# do.net
KiCad netlist of a schematic drawn in Altium Designer
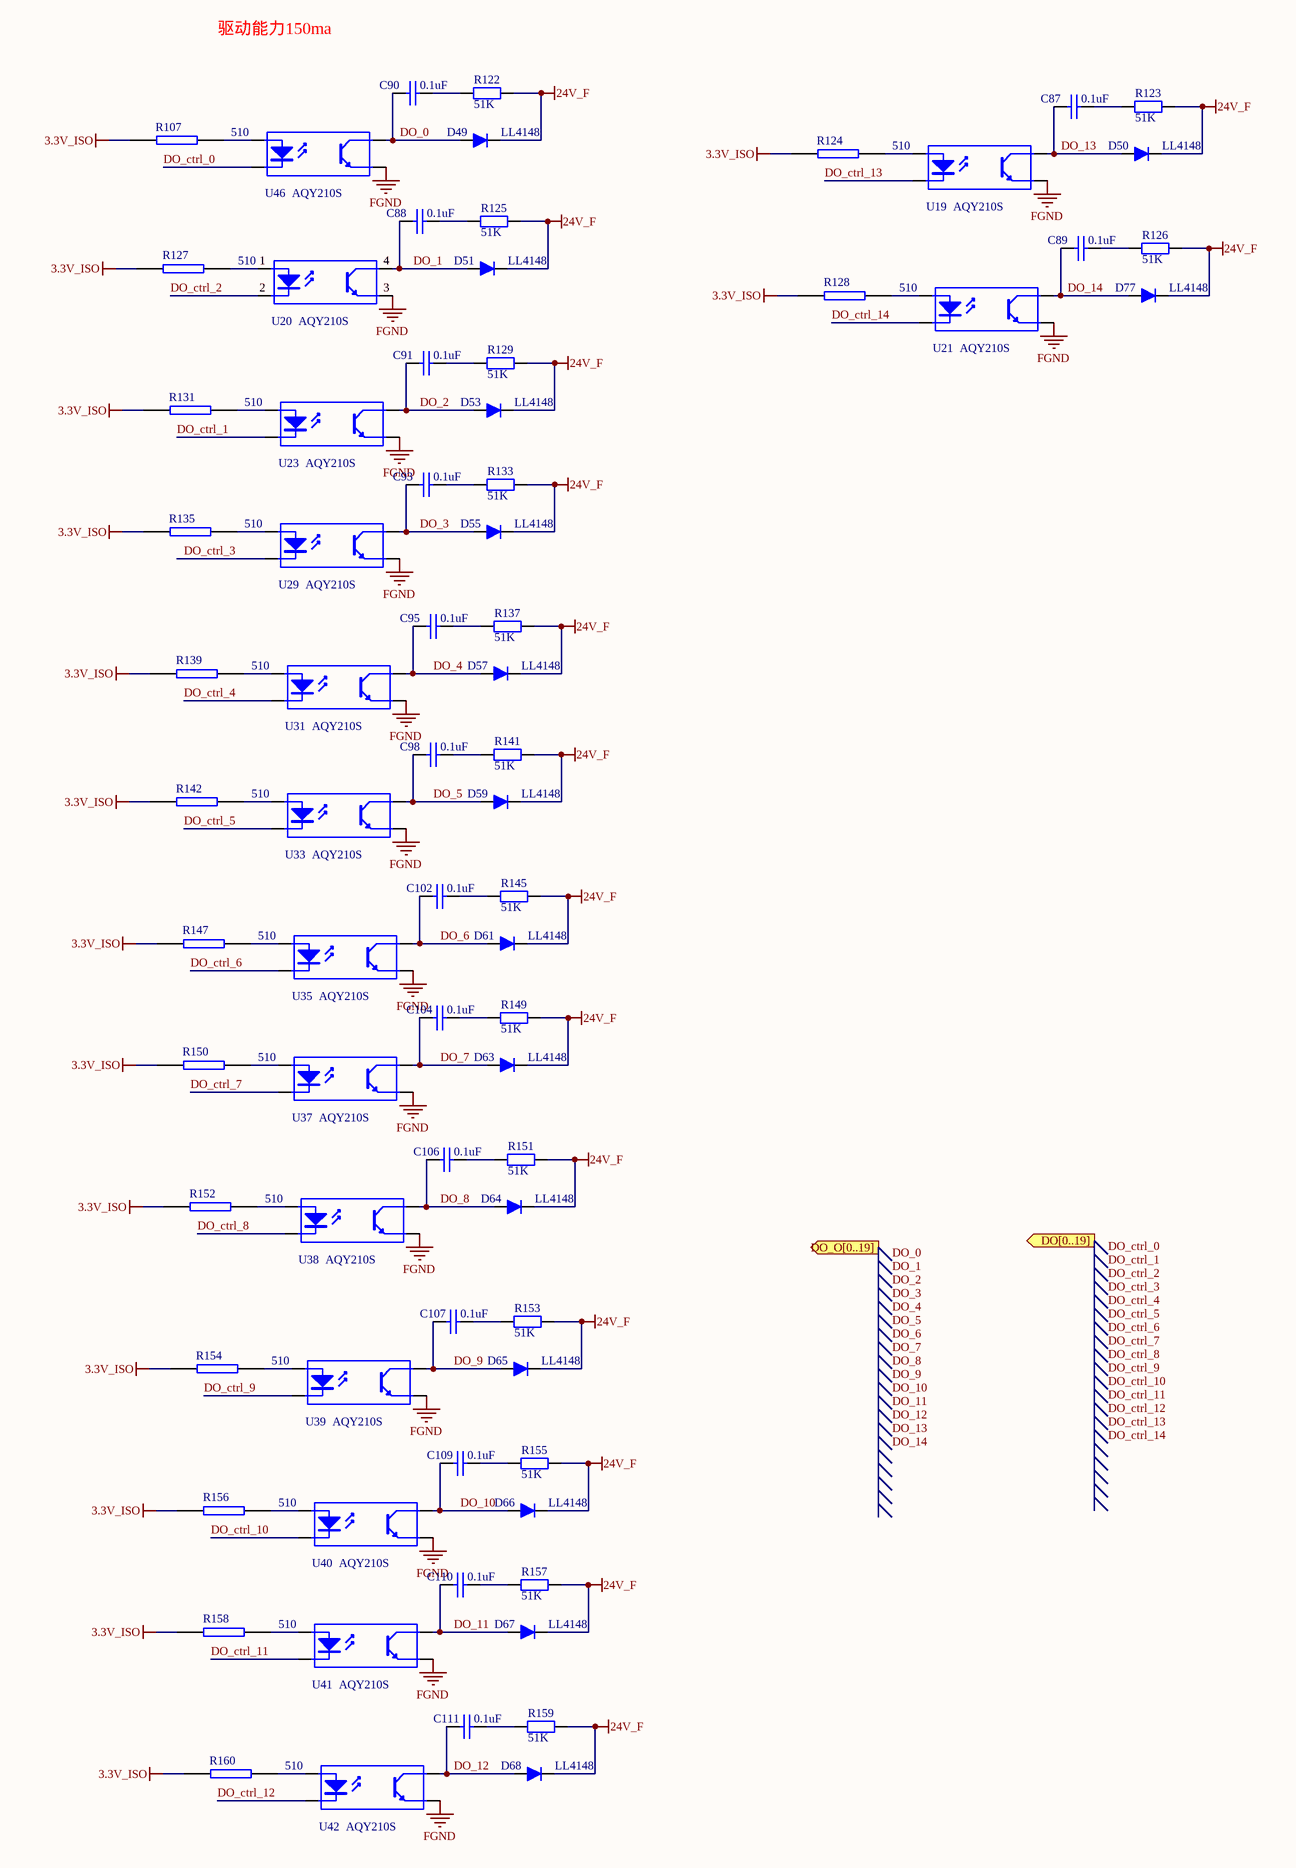
[diagram p0: do.SchDoc]

(export (version "E")
  (design (tool "Eeschema 10.0.6"))
  (components
    (comp (ref "C87")
      (value "0.1uF")
      (footprint "0603C")
      (description "Capacitor")
      (libsource (lib "*") (part "CAP"))
    )
    (comp (ref "C88")
      (value "0.1uF")
      (footprint "0603C")
      (description "Capacitor")
      (libsource (lib "*") (part "CAP"))
    )
    (comp (ref "C89")
      (value "0.1uF")
      (footprint "0603C")
      (description "Capacitor")
      (libsource (lib "*") (part "CAP"))
    )
    (comp (ref "C90")
      (value "0.1uF")
      (footprint "0603C")
      (description "Capacitor")
      (libsource (lib "*") (part "CAP"))
    )
    (comp (ref "C91")
      (value "0.1uF")
      (footprint "0603C")
      (description "Capacitor")
      (libsource (lib "*") (part "CAP"))
    )
    (comp (ref "C93")
      (value "0.1uF")
      (footprint "0603C")
      (description "Capacitor")
      (libsource (lib "*") (part "CAP"))
    )
    (comp (ref "C95")
      (value "0.1uF")
      (footprint "0603C")
      (description "Capacitor")
      (libsource (lib "*") (part "CAP"))
    )
    (comp (ref "C98")
      (value "0.1uF")
      (footprint "0603C")
      (description "Capacitor")
      (libsource (lib "*") (part "CAP"))
    )
    (comp (ref "C102")
      (value "0.1uF")
      (footprint "0603C")
      (description "Capacitor")
      (libsource (lib "*") (part "CAP"))
    )
    (comp (ref "C104")
      (value "0.1uF")
      (footprint "0603C")
      (description "Capacitor")
      (libsource (lib "*") (part "CAP"))
    )
    (comp (ref "C106")
      (value "0.1uF")
      (footprint "0603C")
      (description "Capacitor")
      (libsource (lib "*") (part "CAP"))
    )
    (comp (ref "C107")
      (value "0.1uF")
      (footprint "0603C")
      (description "Capacitor")
      (libsource (lib "*") (part "CAP"))
    )
    (comp (ref "C109")
      (value "0.1uF")
      (footprint "0603C")
      (description "Capacitor")
      (libsource (lib "*") (part "CAP"))
    )
    (comp (ref "C110")
      (value "0.1uF")
      (footprint "0603C")
      (description "Capacitor")
      (libsource (lib "*") (part "CAP"))
    )
    (comp (ref "C111")
      (value "0.1uF")
      (footprint "0603C")
      (description "Capacitor")
      (libsource (lib "*") (part "CAP"))
    )
    (comp (ref "D49")
      (value "LL4148")
      (footprint "DO-213AB/LL34/MiniMELF")
      (description "VISHAY,LL4148,圆柱体MiniMELF100V/2A,ROHS")
      (libsource (lib "Device2018") (part "LL4148"))
    )
    (comp (ref "D50")
      (value "LL4148")
      (footprint "DO-213AB/LL34/MiniMELF")
      (description "VISHAY,LL4148,圆柱体MiniMELF100V/2A,ROHS")
      (libsource (lib "Device2018") (part "LL4148"))
    )
    (comp (ref "D51")
      (value "LL4148")
      (footprint "DO-213AB/LL34/MiniMELF")
      (description "VISHAY,LL4148,圆柱体MiniMELF100V/2A,ROHS")
      (libsource (lib "Device2018") (part "LL4148"))
    )
    (comp (ref "D53")
      (value "LL4148")
      (footprint "DO-213AB/LL34/MiniMELF")
      (description "VISHAY,LL4148,圆柱体MiniMELF100V/2A,ROHS")
      (libsource (lib "Device2018") (part "LL4148"))
    )
    (comp (ref "D55")
      (value "LL4148")
      (footprint "DO-213AB/LL34/MiniMELF")
      (description "VISHAY,LL4148,圆柱体MiniMELF100V/2A,ROHS")
      (libsource (lib "Device2018") (part "LL4148"))
    )
    (comp (ref "D57")
      (value "LL4148")
      (footprint "DO-213AB/LL34/MiniMELF")
      (description "VISHAY,LL4148,圆柱体MiniMELF100V/2A,ROHS")
      (libsource (lib "Device2018") (part "LL4148"))
    )
    (comp (ref "D59")
      (value "LL4148")
      (footprint "DO-213AB/LL34/MiniMELF")
      (description "VISHAY,LL4148,圆柱体MiniMELF100V/2A,ROHS")
      (libsource (lib "Device2018") (part "LL4148"))
    )
    (comp (ref "D61")
      (value "LL4148")
      (footprint "DO-213AB/LL34/MiniMELF")
      (description "VISHAY,LL4148,圆柱体MiniMELF100V/2A,ROHS")
      (libsource (lib "Device2018") (part "LL4148"))
    )
    (comp (ref "D63")
      (value "LL4148")
      (footprint "DO-213AB/LL34/MiniMELF")
      (description "VISHAY,LL4148,圆柱体MiniMELF100V/2A,ROHS")
      (libsource (lib "Device2018") (part "LL4148"))
    )
    (comp (ref "D64")
      (value "LL4148")
      (footprint "DO-213AB/LL34/MiniMELF")
      (description "VISHAY,LL4148,圆柱体MiniMELF100V/2A,ROHS")
      (libsource (lib "Device2018") (part "LL4148"))
    )
    (comp (ref "D65")
      (value "LL4148")
      (footprint "DO-213AB/LL34/MiniMELF")
      (description "VISHAY,LL4148,圆柱体MiniMELF100V/2A,ROHS")
      (libsource (lib "Device2018") (part "LL4148"))
    )
    (comp (ref "D66")
      (value "LL4148")
      (footprint "DO-213AB/LL34/MiniMELF")
      (description "VISHAY,LL4148,圆柱体MiniMELF100V/2A,ROHS")
      (libsource (lib "Device2018") (part "LL4148"))
    )
    (comp (ref "D67")
      (value "LL4148")
      (footprint "DO-213AB/LL34/MiniMELF")
      (description "VISHAY,LL4148,圆柱体MiniMELF100V/2A,ROHS")
      (libsource (lib "Device2018") (part "LL4148"))
    )
    (comp (ref "D68")
      (value "LL4148")
      (footprint "DO-213AB/LL34/MiniMELF")
      (description "VISHAY,LL4148,圆柱体MiniMELF100V/2A,ROHS")
      (libsource (lib "Device2018") (part "LL4148"))
    )
    (comp (ref "D77")
      (value "LL4148")
      (footprint "DO-213AB/LL34/MiniMELF")
      (description "VISHAY,LL4148,圆柱体MiniMELF100V/2A,ROHS")
      (libsource (lib "Device2018") (part "LL4148"))
    )
    (comp (ref "R107") (value "510") (footprint "0603R") (libsource (lib "*") (part "RES2")))
    (comp (ref "R122") (value "51K") (footprint "0603R") (libsource (lib "MQlibrary") (part "Res0805M")))
    (comp (ref "R123") (value "51K") (footprint "0603R") (libsource (lib "MQlibrary") (part "Res0805M")))
    (comp (ref "R124") (value "510") (footprint "0603R") (libsource (lib "*") (part "RES2")))
    (comp (ref "R125") (value "51K") (footprint "0603R") (libsource (lib "MQlibrary") (part "Res0805M")))
    (comp (ref "R126") (value "51K") (footprint "0603R") (libsource (lib "MQlibrary") (part "Res0805M")))
    (comp (ref "R127") (value "510") (footprint "0603R") (libsource (lib "*") (part "RES2")))
    (comp (ref "R128") (value "510") (footprint "0603R") (libsource (lib "*") (part "RES2")))
    (comp (ref "R129") (value "51K") (footprint "0603R") (libsource (lib "MQlibrary") (part "Res0805M")))
    (comp (ref "R131") (value "510") (footprint "0603R") (libsource (lib "*") (part "RES2")))
    (comp (ref "R133") (value "51K") (footprint "0603R") (libsource (lib "MQlibrary") (part "Res0805M")))
    (comp (ref "R135") (value "510") (footprint "0603R") (libsource (lib "*") (part "RES2")))
    (comp (ref "R137") (value "51K") (footprint "0603R") (libsource (lib "MQlibrary") (part "Res0805M")))
    (comp (ref "R139") (value "510") (footprint "0603R") (libsource (lib "*") (part "RES2")))
    (comp (ref "R141") (value "51K") (footprint "0603R") (libsource (lib "MQlibrary") (part "Res0805M")))
    (comp (ref "R142") (value "510") (footprint "0603R") (libsource (lib "*") (part "RES2")))
    (comp (ref "R145") (value "51K") (footprint "0603R") (libsource (lib "MQlibrary") (part "Res0805M")))
    (comp (ref "R147") (value "510") (footprint "0603R") (libsource (lib "*") (part "RES2")))
    (comp (ref "R149") (value "51K") (footprint "0603R") (libsource (lib "MQlibrary") (part "Res0805M")))
    (comp (ref "R150") (value "510") (footprint "0603R") (libsource (lib "*") (part "RES2")))
    (comp (ref "R151") (value "51K") (footprint "0603R") (libsource (lib "MQlibrary") (part "Res0805M")))
    (comp (ref "R152") (value "510") (footprint "0603R") (libsource (lib "*") (part "RES2")))
    (comp (ref "R153") (value "51K") (footprint "0603R") (libsource (lib "MQlibrary") (part "Res0805M")))
    (comp (ref "R154") (value "510") (footprint "0603R") (libsource (lib "*") (part "RES2")))
    (comp (ref "R155") (value "51K") (footprint "0603R") (libsource (lib "MQlibrary") (part "Res0805M")))
    (comp (ref "R156") (value "510") (footprint "0603R") (libsource (lib "*") (part "RES2")))
    (comp (ref "R157") (value "51K") (footprint "0603R") (libsource (lib "MQlibrary") (part "Res0805M")))
    (comp (ref "R158") (value "510") (footprint "0603R") (libsource (lib "*") (part "RES2")))
    (comp (ref "R159") (value "51K") (footprint "0603R") (libsource (lib "MQlibrary") (part "Res0805M")))
    (comp (ref "R160") (value "510") (footprint "0603R") (libsource (lib "*") (part "RES2")))
    (comp (ref "U19")
      (value "AQY210S")
      (footprint "sop4")
      (description "4-Pin Phototransistor Optocoupler")
      (fields (field (name "PUBLISHER") "Altium Limited"))
      (libsource (lib "Miscellaneous Devices") (part "Optoisolator1"))
    )
    (comp (ref "U20")
      (value "AQY210S")
      (footprint "sop4")
      (description "4-Pin Phototransistor Optocoupler")
      (fields (field (name "PUBLISHER") "Altium Limited"))
      (libsource (lib "") (part "Optoisolator1_1"))
    )
    (comp (ref "U21")
      (value "AQY210S")
      (footprint "sop4")
      (description "4-Pin Phototransistor Optocoupler")
      (fields (field (name "PUBLISHER") "Altium Limited"))
      (libsource (lib "Miscellaneous Devices") (part "Optoisolator1"))
    )
    (comp (ref "U23")
      (value "AQY210S")
      (footprint "sop4")
      (description "4-Pin Phototransistor Optocoupler")
      (fields (field (name "PUBLISHER") "Altium Limited"))
      (libsource (lib "Miscellaneous Devices") (part "Optoisolator1"))
    )
    (comp (ref "U29")
      (value "AQY210S")
      (footprint "sop4")
      (description "4-Pin Phototransistor Optocoupler")
      (fields (field (name "PUBLISHER") "Altium Limited"))
      (libsource (lib "Miscellaneous Devices") (part "Optoisolator1"))
    )
    (comp (ref "U31")
      (value "AQY210S")
      (footprint "sop4")
      (description "4-Pin Phototransistor Optocoupler")
      (fields (field (name "PUBLISHER") "Altium Limited"))
      (libsource (lib "Miscellaneous Devices") (part "Optoisolator1"))
    )
    (comp (ref "U33")
      (value "AQY210S")
      (footprint "sop4")
      (description "4-Pin Phototransistor Optocoupler")
      (fields (field (name "PUBLISHER") "Altium Limited"))
      (libsource (lib "Miscellaneous Devices") (part "Optoisolator1"))
    )
    (comp (ref "U35")
      (value "AQY210S")
      (footprint "sop4")
      (description "4-Pin Phototransistor Optocoupler")
      (fields (field (name "PUBLISHER") "Altium Limited"))
      (libsource (lib "Miscellaneous Devices") (part "Optoisolator1"))
    )
    (comp (ref "U37")
      (value "AQY210S")
      (footprint "sop4")
      (description "4-Pin Phototransistor Optocoupler")
      (fields (field (name "PUBLISHER") "Altium Limited"))
      (libsource (lib "Miscellaneous Devices") (part "Optoisolator1"))
    )
    (comp (ref "U38")
      (value "AQY210S")
      (footprint "sop4")
      (description "4-Pin Phototransistor Optocoupler")
      (fields (field (name "PUBLISHER") "Altium Limited"))
      (libsource (lib "Miscellaneous Devices") (part "Optoisolator1"))
    )
    (comp (ref "U39")
      (value "AQY210S")
      (footprint "sop4")
      (description "4-Pin Phototransistor Optocoupler")
      (fields (field (name "PUBLISHER") "Altium Limited"))
      (libsource (lib "Miscellaneous Devices") (part "Optoisolator1"))
    )
    (comp (ref "U40")
      (value "AQY210S")
      (footprint "sop4")
      (description "4-Pin Phototransistor Optocoupler")
      (fields (field (name "PUBLISHER") "Altium Limited"))
      (libsource (lib "Miscellaneous Devices") (part "Optoisolator1"))
    )
    (comp (ref "U41")
      (value "AQY210S")
      (footprint "sop4")
      (description "4-Pin Phototransistor Optocoupler")
      (fields (field (name "PUBLISHER") "Altium Limited"))
      (libsource (lib "Miscellaneous Devices") (part "Optoisolator1"))
    )
    (comp (ref "U42")
      (value "AQY210S")
      (footprint "sop4")
      (description "4-Pin Phototransistor Optocoupler")
      (fields (field (name "PUBLISHER") "Altium Limited"))
      (libsource (lib "Miscellaneous Devices") (part "Optoisolator1"))
    )
    (comp (ref "U46")
      (value "AQY210S")
      (footprint "sop4")
      (description "4-Pin Phototransistor Optocoupler")
      (fields (field (name "PUBLISHER") "Altium Limited"))
      (libsource (lib "Miscellaneous Devices") (part "Optoisolator1"))
    )
  )
  (nets
    (net (code "42") (name "/DO_0") (class "Default")
      (node (ref "C90") (pin "1") (pinfunction "1_1") (pintype "passive"))
      (node (ref "D49") (pin "2") (pinfunction "2_2") (pintype "passive"))
      (node (ref "U46") (pin "4") (pinfunction "C_4") (pintype "passive"))
    )
    (net (code "43") (name "/DO_1") (class "Default")
      (node (ref "C88") (pin "1") (pinfunction "1_1") (pintype "passive"))
      (node (ref "D51") (pin "2") (pinfunction "2_2") (pintype "passive"))
      (node (ref "U20") (pin "4") (pinfunction "C_4") (pintype "passive"))
    )
    (net (code "44") (name "/DO_2") (class "Default")
      (node (ref "C91") (pin "1") (pinfunction "1_1") (pintype "passive"))
      (node (ref "D53") (pin "2") (pinfunction "2_2") (pintype "passive"))
      (node (ref "U23") (pin "4") (pinfunction "C_4") (pintype "passive"))
    )
    (net (code "45") (name "/DO_3") (class "Default")
      (node (ref "C93") (pin "1") (pinfunction "1_1") (pintype "passive"))
      (node (ref "D55") (pin "2") (pinfunction "2_2") (pintype "passive"))
      (node (ref "U29") (pin "4") (pinfunction "C_4") (pintype "passive"))
    )
    (net (code "46") (name "/DO_4") (class "Default")
      (node (ref "C95") (pin "1") (pinfunction "1_1") (pintype "passive"))
      (node (ref "D57") (pin "2") (pinfunction "2_2") (pintype "passive"))
      (node (ref "U31") (pin "4") (pinfunction "C_4") (pintype "passive"))
    )
    (net (code "47") (name "/DO_5") (class "Default")
      (node (ref "C98") (pin "1") (pinfunction "1_1") (pintype "passive"))
      (node (ref "D59") (pin "2") (pinfunction "2_2") (pintype "passive"))
      (node (ref "U33") (pin "4") (pinfunction "C_4") (pintype "passive"))
    )
    (net (code "48") (name "/DO_6") (class "Default")
      (node (ref "C102") (pin "1") (pinfunction "1_1") (pintype "passive"))
      (node (ref "D61") (pin "2") (pinfunction "2_2") (pintype "passive"))
      (node (ref "U35") (pin "4") (pinfunction "C_4") (pintype "passive"))
    )
    (net (code "49") (name "/DO_7") (class "Default")
      (node (ref "C104") (pin "1") (pinfunction "1_1") (pintype "passive"))
      (node (ref "D63") (pin "2") (pinfunction "2_2") (pintype "passive"))
      (node (ref "U37") (pin "4") (pinfunction "C_4") (pintype "passive"))
    )
    (net (code "50") (name "/DO_8") (class "Default")
      (node (ref "C106") (pin "1") (pinfunction "1_1") (pintype "passive"))
      (node (ref "D64") (pin "2") (pinfunction "2_2") (pintype "passive"))
      (node (ref "U38") (pin "4") (pinfunction "C_4") (pintype "passive"))
    )
    (net (code "51") (name "/DO_9") (class "Default")
      (node (ref "C107") (pin "1") (pinfunction "1_1") (pintype "passive"))
      (node (ref "D65") (pin "2") (pinfunction "2_2") (pintype "passive"))
      (node (ref "U39") (pin "4") (pinfunction "C_4") (pintype "passive"))
    )
    (net (code "52") (name "/DO_10") (class "Default")
      (node (ref "C109") (pin "1") (pinfunction "1_1") (pintype "passive"))
      (node (ref "D66") (pin "2") (pinfunction "2_2") (pintype "passive"))
      (node (ref "U40") (pin "4") (pinfunction "C_4") (pintype "passive"))
    )
    (net (code "53") (name "/DO_11") (class "Default")
      (node (ref "C110") (pin "1") (pinfunction "1_1") (pintype "passive"))
      (node (ref "D67") (pin "2") (pinfunction "2_2") (pintype "passive"))
      (node (ref "U41") (pin "4") (pinfunction "C_4") (pintype "passive"))
    )
    (net (code "54") (name "/DO_12") (class "Default")
      (node (ref "C111") (pin "1") (pinfunction "1_1") (pintype "passive"))
      (node (ref "D68") (pin "2") (pinfunction "2_2") (pintype "passive"))
      (node (ref "U42") (pin "4") (pinfunction "C_4") (pintype "passive"))
    )
    (net (code "55") (name "/DO_13") (class "Default")
      (node (ref "C87") (pin "1") (pinfunction "1_1") (pintype "passive"))
      (node (ref "D50") (pin "2") (pinfunction "2_2") (pintype "passive"))
      (node (ref "U19") (pin "4") (pinfunction "C_4") (pintype "passive"))
    )
    (net (code "56") (name "/DO_14") (class "Default")
      (node (ref "C89") (pin "1") (pinfunction "1_1") (pintype "passive"))
      (node (ref "D77") (pin "2") (pinfunction "2_2") (pintype "passive"))
      (node (ref "U21") (pin "4") (pinfunction "C_4") (pintype "passive"))
    )
    (net (code "58") (name "/DO_ctrl_0") (class "Default")
      (node (ref "U46") (pin "2") (pinfunction "K_2") (pintype "passive"))
    )
    (net (code "59") (name "/DO_ctrl_1") (class "Default")
      (node (ref "U23") (pin "2") (pinfunction "K_2") (pintype "passive"))
    )
    (net (code "60") (name "/DO_ctrl_2") (class "Default")
      (node (ref "U20") (pin "2") (pinfunction "K_2") (pintype "passive"))
    )
    (net (code "61") (name "/DO_ctrl_3") (class "Default")
      (node (ref "U29") (pin "2") (pinfunction "K_2") (pintype "passive"))
    )
    (net (code "62") (name "/DO_ctrl_4") (class "Default")
      (node (ref "U31") (pin "2") (pinfunction "K_2") (pintype "passive"))
    )
    (net (code "63") (name "/DO_ctrl_5") (class "Default")
      (node (ref "U33") (pin "2") (pinfunction "K_2") (pintype "passive"))
    )
    (net (code "64") (name "/DO_ctrl_6") (class "Default")
      (node (ref "U35") (pin "2") (pinfunction "K_2") (pintype "passive"))
    )
    (net (code "65") (name "/DO_ctrl_7") (class "Default")
      (node (ref "U37") (pin "2") (pinfunction "K_2") (pintype "passive"))
    )
    (net (code "66") (name "/DO_ctrl_8") (class "Default")
      (node (ref "U38") (pin "2") (pinfunction "K_2") (pintype "passive"))
    )
    (net (code "67") (name "/DO_ctrl_9") (class "Default")
      (node (ref "U39") (pin "2") (pinfunction "K_2") (pintype "passive"))
    )
    (net (code "68") (name "/DO_ctrl_10") (class "Default")
      (node (ref "U40") (pin "2") (pinfunction "K_2") (pintype "passive"))
    )
    (net (code "69") (name "/DO_ctrl_11") (class "Default")
      (node (ref "U41") (pin "2") (pinfunction "K_2") (pintype "passive"))
    )
    (net (code "70") (name "/DO_ctrl_12") (class "Default")
      (node (ref "U42") (pin "2") (pinfunction "K_2") (pintype "passive"))
    )
    (net (code "71") (name "/DO_ctrl_13") (class "Default")
      (node (ref "U19") (pin "2") (pinfunction "K_2") (pintype "passive"))
    )
    (net (code "72") (name "/DO_ctrl_14") (class "Default")
      (node (ref "U21") (pin "2") (pinfunction "K_2") (pintype "passive"))
    )
    (net (code "73") (name "3.3V_ISO") (class "Default")
      (node (ref "R107") (pin "2") (pinfunction "2_2") (pintype "passive"))
      (node (ref "R124") (pin "2") (pinfunction "2_2") (pintype "passive"))
      (node (ref "R127") (pin "2") (pinfunction "2_2") (pintype "passive"))
      (node (ref "R128") (pin "2") (pinfunction "2_2") (pintype "passive"))
      (node (ref "R131") (pin "2") (pinfunction "2_2") (pintype "passive"))
      (node (ref "R135") (pin "2") (pinfunction "2_2") (pintype "passive"))
      (node (ref "R139") (pin "2") (pinfunction "2_2") (pintype "passive"))
      (node (ref "R142") (pin "2") (pinfunction "2_2") (pintype "passive"))
      (node (ref "R147") (pin "2") (pinfunction "2_2") (pintype "passive"))
      (node (ref "R150") (pin "2") (pinfunction "2_2") (pintype "passive"))
      (node (ref "R152") (pin "2") (pinfunction "2_2") (pintype "passive"))
      (node (ref "R154") (pin "2") (pinfunction "2_2") (pintype "passive"))
      (node (ref "R156") (pin "2") (pinfunction "2_2") (pintype "passive"))
      (node (ref "R158") (pin "2") (pinfunction "2_2") (pintype "passive"))
      (node (ref "R160") (pin "2") (pinfunction "2_2") (pintype "passive"))
    )
    (net (code "74") (name "24V_F") (class "Default")
      (node (ref "D49") (pin "1") (pinfunction "1_1") (pintype "passive"))
      (node (ref "D50") (pin "1") (pinfunction "1_1") (pintype "passive"))
      (node (ref "D51") (pin "1") (pinfunction "1_1") (pintype "passive"))
      (node (ref "D53") (pin "1") (pinfunction "1_1") (pintype "passive"))
      (node (ref "D55") (pin "1") (pinfunction "1_1") (pintype "passive"))
      (node (ref "D57") (pin "1") (pinfunction "1_1") (pintype "passive"))
      (node (ref "D59") (pin "1") (pinfunction "1_1") (pintype "passive"))
      (node (ref "D61") (pin "1") (pinfunction "1_1") (pintype "passive"))
      (node (ref "D63") (pin "1") (pinfunction "1_1") (pintype "passive"))
      (node (ref "D64") (pin "1") (pinfunction "1_1") (pintype "passive"))
      (node (ref "D65") (pin "1") (pinfunction "1_1") (pintype "passive"))
      (node (ref "D66") (pin "1") (pinfunction "1_1") (pintype "passive"))
      (node (ref "D67") (pin "1") (pinfunction "1_1") (pintype "passive"))
      (node (ref "D68") (pin "1") (pinfunction "1_1") (pintype "passive"))
      (node (ref "D77") (pin "1") (pinfunction "1_1") (pintype "passive"))
      (node (ref "R122") (pin "2") (pinfunction "2_2") (pintype "passive"))
      (node (ref "R123") (pin "2") (pinfunction "2_2") (pintype "passive"))
      (node (ref "R125") (pin "2") (pinfunction "2_2") (pintype "passive"))
      (node (ref "R126") (pin "2") (pinfunction "2_2") (pintype "passive"))
      (node (ref "R129") (pin "2") (pinfunction "2_2") (pintype "passive"))
      (node (ref "R133") (pin "2") (pinfunction "2_2") (pintype "passive"))
      (node (ref "R137") (pin "2") (pinfunction "2_2") (pintype "passive"))
      (node (ref "R141") (pin "2") (pinfunction "2_2") (pintype "passive"))
      (node (ref "R145") (pin "2") (pinfunction "2_2") (pintype "passive"))
      (node (ref "R149") (pin "2") (pinfunction "2_2") (pintype "passive"))
      (node (ref "R151") (pin "2") (pinfunction "2_2") (pintype "passive"))
      (node (ref "R153") (pin "2") (pinfunction "2_2") (pintype "passive"))
      (node (ref "R155") (pin "2") (pinfunction "2_2") (pintype "passive"))
      (node (ref "R157") (pin "2") (pinfunction "2_2") (pintype "passive"))
      (node (ref "R159") (pin "2") (pinfunction "2_2") (pintype "passive"))
    )
    (net (code "75") (name "FGND") (class "Default")
      (node (ref "U19") (pin "3") (pinfunction "E_3") (pintype "passive"))
      (node (ref "U20") (pin "3") (pinfunction "E_3") (pintype "passive"))
      (node (ref "U21") (pin "3") (pinfunction "E_3") (pintype "passive"))
      (node (ref "U23") (pin "3") (pinfunction "E_3") (pintype "passive"))
      (node (ref "U29") (pin "3") (pinfunction "E_3") (pintype "passive"))
      (node (ref "U31") (pin "3") (pinfunction "E_3") (pintype "passive"))
      (node (ref "U33") (pin "3") (pinfunction "E_3") (pintype "passive"))
      (node (ref "U35") (pin "3") (pinfunction "E_3") (pintype "passive"))
      (node (ref "U37") (pin "3") (pinfunction "E_3") (pintype "passive"))
      (node (ref "U38") (pin "3") (pinfunction "E_3") (pintype "passive"))
      (node (ref "U39") (pin "3") (pinfunction "E_3") (pintype "passive"))
      (node (ref "U40") (pin "3") (pinfunction "E_3") (pintype "passive"))
      (node (ref "U41") (pin "3") (pinfunction "E_3") (pintype "passive"))
      (node (ref "U42") (pin "3") (pinfunction "E_3") (pintype "passive"))
      (node (ref "U46") (pin "3") (pinfunction "E_3") (pintype "passive"))
    )
    (net (code "76") (name "Net-(C87-Pad2)") (class "Default")
      (node (ref "C87") (pin "2") (pinfunction "2_2") (pintype "passive"))
      (node (ref "R123") (pin "1") (pinfunction "1_1") (pintype "passive"))
    )
    (net (code "77") (name "Net-(C88-Pad2)") (class "Default")
      (node (ref "C88") (pin "2") (pinfunction "2_2") (pintype "passive"))
      (node (ref "R125") (pin "1") (pinfunction "1_1") (pintype "passive"))
    )
    (net (code "78") (name "Net-(C89-Pad2)") (class "Default")
      (node (ref "C89") (pin "2") (pinfunction "2_2") (pintype "passive"))
      (node (ref "R126") (pin "1") (pinfunction "1_1") (pintype "passive"))
    )
    (net (code "79") (name "Net-(C90-Pad2)") (class "Default")
      (node (ref "C90") (pin "2") (pinfunction "2_2") (pintype "passive"))
      (node (ref "R122") (pin "1") (pinfunction "1_1") (pintype "passive"))
    )
    (net (code "80") (name "Net-(C91-Pad2)") (class "Default")
      (node (ref "C91") (pin "2") (pinfunction "2_2") (pintype "passive"))
      (node (ref "R129") (pin "1") (pinfunction "1_1") (pintype "passive"))
    )
    (net (code "81") (name "Net-(C93-Pad2)") (class "Default")
      (node (ref "C93") (pin "2") (pinfunction "2_2") (pintype "passive"))
      (node (ref "R133") (pin "1") (pinfunction "1_1") (pintype "passive"))
    )
    (net (code "82") (name "Net-(C95-Pad2)") (class "Default")
      (node (ref "C95") (pin "2") (pinfunction "2_2") (pintype "passive"))
      (node (ref "R137") (pin "1") (pinfunction "1_1") (pintype "passive"))
    )
    (net (code "83") (name "Net-(C98-Pad2)") (class "Default")
      (node (ref "C98") (pin "2") (pinfunction "2_2") (pintype "passive"))
      (node (ref "R141") (pin "1") (pinfunction "1_1") (pintype "passive"))
    )
    (net (code "84") (name "Net-(C102-Pad2)") (class "Default")
      (node (ref "C102") (pin "2") (pinfunction "2_2") (pintype "passive"))
      (node (ref "R145") (pin "1") (pinfunction "1_1") (pintype "passive"))
    )
    (net (code "85") (name "Net-(C104-Pad2)") (class "Default")
      (node (ref "C104") (pin "2") (pinfunction "2_2") (pintype "passive"))
      (node (ref "R149") (pin "1") (pinfunction "1_1") (pintype "passive"))
    )
    (net (code "86") (name "Net-(C106-Pad2)") (class "Default")
      (node (ref "C106") (pin "2") (pinfunction "2_2") (pintype "passive"))
      (node (ref "R151") (pin "1") (pinfunction "1_1") (pintype "passive"))
    )
    (net (code "87") (name "Net-(C107-Pad2)") (class "Default")
      (node (ref "C107") (pin "2") (pinfunction "2_2") (pintype "passive"))
      (node (ref "R153") (pin "1") (pinfunction "1_1") (pintype "passive"))
    )
    (net (code "88") (name "Net-(C109-Pad2)") (class "Default")
      (node (ref "C109") (pin "2") (pinfunction "2_2") (pintype "passive"))
      (node (ref "R155") (pin "1") (pinfunction "1_1") (pintype "passive"))
    )
    (net (code "89") (name "Net-(C110-Pad2)") (class "Default")
      (node (ref "C110") (pin "2") (pinfunction "2_2") (pintype "passive"))
      (node (ref "R157") (pin "1") (pinfunction "1_1") (pintype "passive"))
    )
    (net (code "90") (name "Net-(C111-Pad2)") (class "Default")
      (node (ref "C111") (pin "2") (pinfunction "2_2") (pintype "passive"))
      (node (ref "R159") (pin "1") (pinfunction "1_1") (pintype "passive"))
    )
    (net (code "91") (name "Net-(U19-A)") (class "Default")
      (node (ref "R124") (pin "1") (pinfunction "1_1") (pintype "passive"))
      (node (ref "U19") (pin "1") (pinfunction "A_1") (pintype "passive"))
    )
    (net (code "92") (name "Net-(U20-A)") (class "Default")
      (node (ref "R127") (pin "1") (pinfunction "1_1") (pintype "passive"))
      (node (ref "U20") (pin "1") (pinfunction "A_1") (pintype "passive"))
    )
    (net (code "93") (name "Net-(U21-A)") (class "Default")
      (node (ref "R128") (pin "1") (pinfunction "1_1") (pintype "passive"))
      (node (ref "U21") (pin "1") (pinfunction "A_1") (pintype "passive"))
    )
    (net (code "94") (name "Net-(U23-A)") (class "Default")
      (node (ref "R131") (pin "1") (pinfunction "1_1") (pintype "passive"))
      (node (ref "U23") (pin "1") (pinfunction "A_1") (pintype "passive"))
    )
    (net (code "95") (name "Net-(U29-A)") (class "Default")
      (node (ref "R135") (pin "1") (pinfunction "1_1") (pintype "passive"))
      (node (ref "U29") (pin "1") (pinfunction "A_1") (pintype "passive"))
    )
    (net (code "96") (name "Net-(U31-A)") (class "Default")
      (node (ref "R139") (pin "1") (pinfunction "1_1") (pintype "passive"))
      (node (ref "U31") (pin "1") (pinfunction "A_1") (pintype "passive"))
    )
    (net (code "97") (name "Net-(U33-A)") (class "Default")
      (node (ref "R142") (pin "1") (pinfunction "1_1") (pintype "passive"))
      (node (ref "U33") (pin "1") (pinfunction "A_1") (pintype "passive"))
    )
    (net (code "98") (name "Net-(U35-A)") (class "Default")
      (node (ref "R147") (pin "1") (pinfunction "1_1") (pintype "passive"))
      (node (ref "U35") (pin "1") (pinfunction "A_1") (pintype "passive"))
    )
    (net (code "99") (name "Net-(U37-A)") (class "Default")
      (node (ref "R150") (pin "1") (pinfunction "1_1") (pintype "passive"))
      (node (ref "U37") (pin "1") (pinfunction "A_1") (pintype "passive"))
    )
    (net (code "100") (name "Net-(U38-A)") (class "Default")
      (node (ref "R152") (pin "1") (pinfunction "1_1") (pintype "passive"))
      (node (ref "U38") (pin "1") (pinfunction "A_1") (pintype "passive"))
    )
    (net (code "101") (name "Net-(U39-A)") (class "Default")
      (node (ref "R154") (pin "1") (pinfunction "1_1") (pintype "passive"))
      (node (ref "U39") (pin "1") (pinfunction "A_1") (pintype "passive"))
    )
    (net (code "102") (name "Net-(U40-A)") (class "Default")
      (node (ref "R156") (pin "1") (pinfunction "1_1") (pintype "passive"))
      (node (ref "U40") (pin "1") (pinfunction "A_1") (pintype "passive"))
    )
    (net (code "103") (name "Net-(U41-A)") (class "Default")
      (node (ref "R158") (pin "1") (pinfunction "1_1") (pintype "passive"))
      (node (ref "U41") (pin "1") (pinfunction "A_1") (pintype "passive"))
    )
    (net (code "104") (name "Net-(U42-A)") (class "Default")
      (node (ref "R160") (pin "1") (pinfunction "1_1") (pintype "passive"))
      (node (ref "U42") (pin "1") (pinfunction "A_1") (pintype "passive"))
    )
    (net (code "105") (name "Net-(U46-A)") (class "Default")
      (node (ref "R107") (pin "1") (pinfunction "1_1") (pintype "passive"))
      (node (ref "U46") (pin "1") (pinfunction "A_1") (pintype "passive"))
    )
  )
)
